# robotito.net
KiCad netlist of a schematic drawn in EAGLE
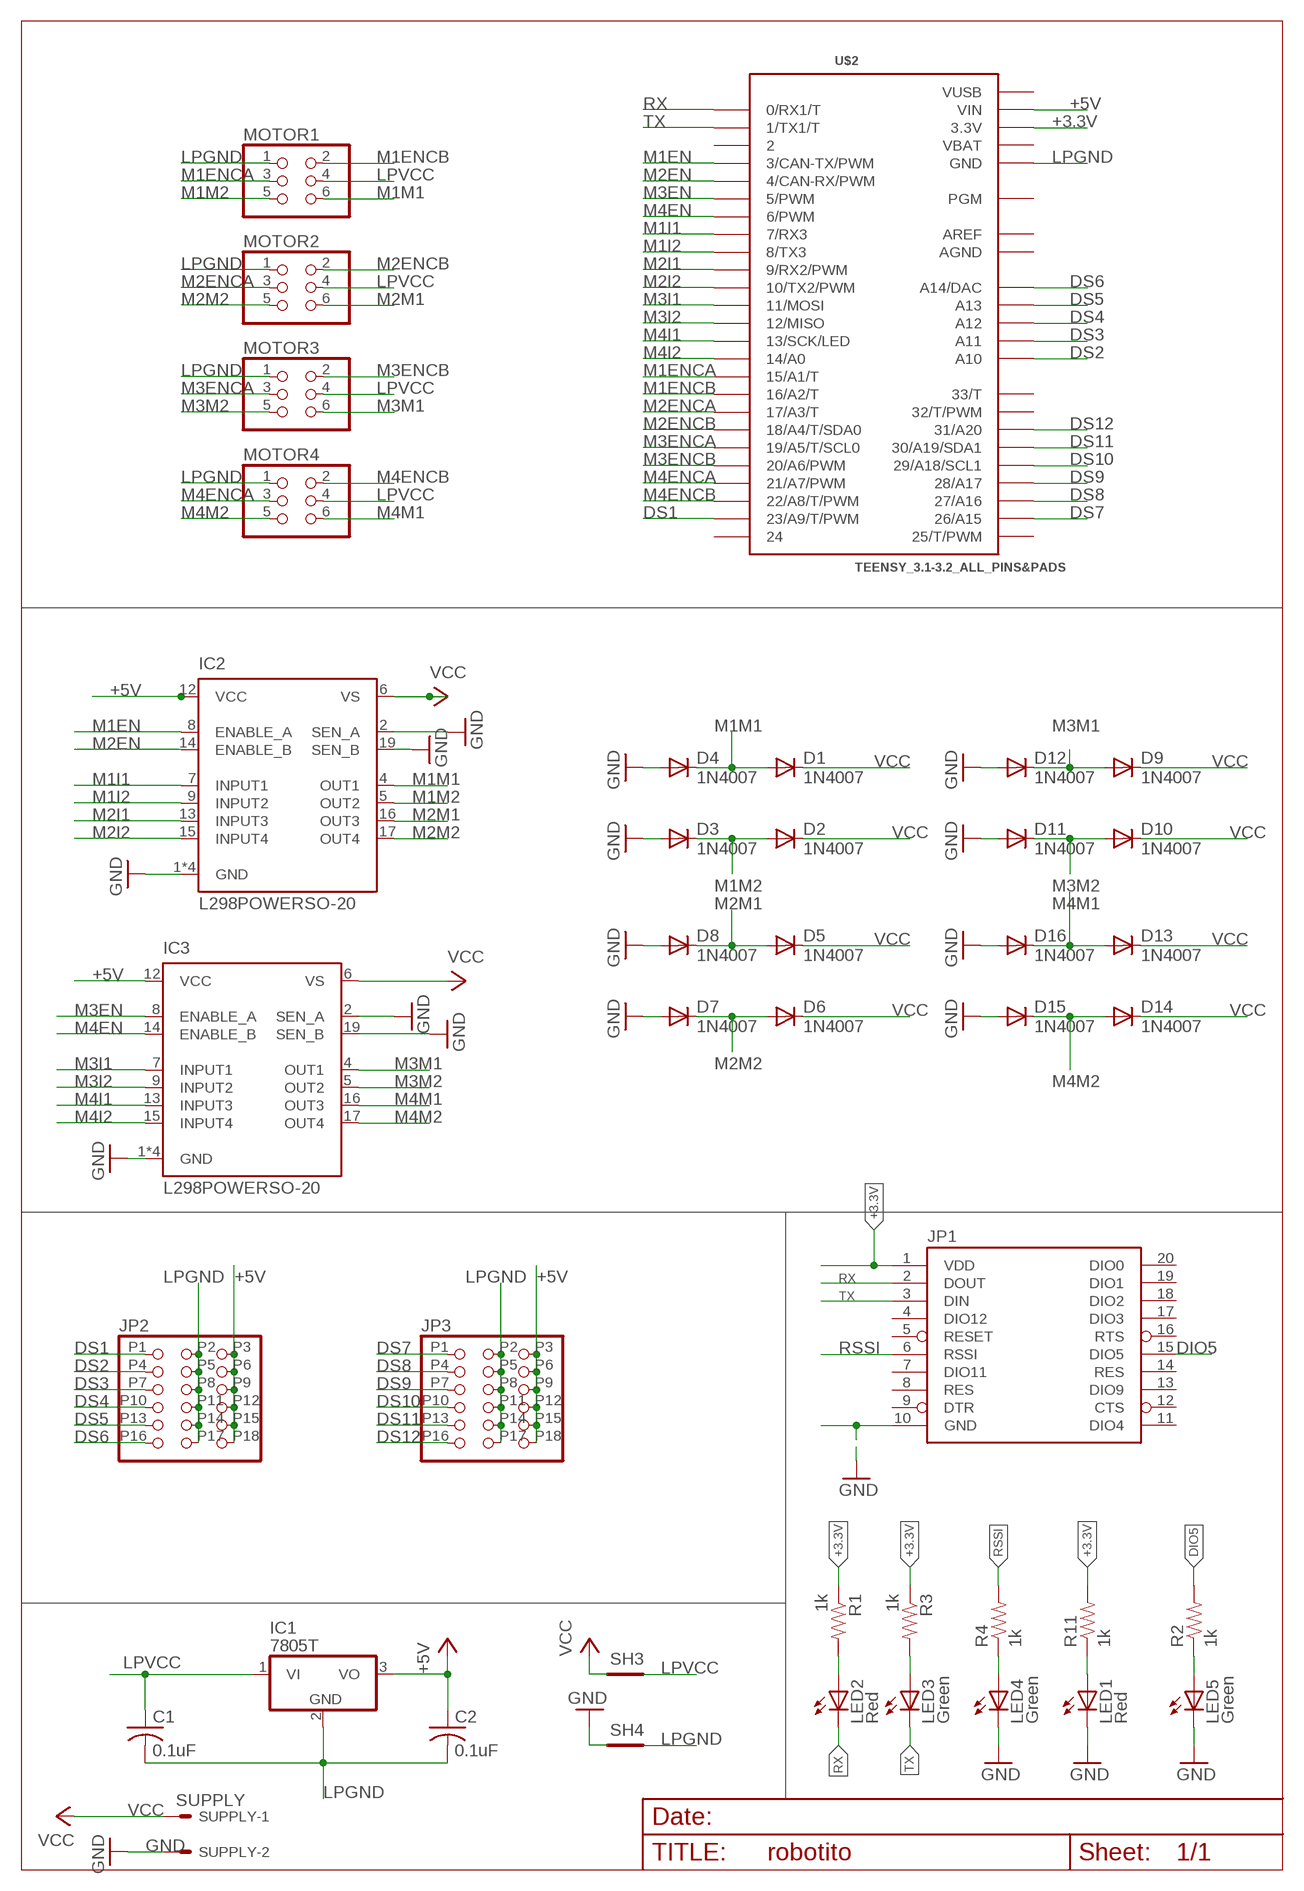
[diagram p0: schematic, sheet 1]

(export (version "E")
  (design (tool "Eeschema 10.0.6"))
  (components
    (comp (ref "C1")
      (value "0.1uF")
      (footprint "eagle-import:C0805")
      (libsource (lib "eagle-import") (part "C-USC0805"))
    )
    (comp (ref "C2")
      (value "0.1uF")
      (footprint "eagle-import:C0805")
      (libsource (lib "eagle-import") (part "C-USC0805"))
    )
    (comp (ref "D1")
      (value "1N4007")
      (footprint "eagle-import:DO41-10")
      (libsource (lib "eagle-import") (part "1N4004"))
    )
    (comp (ref "D2")
      (value "1N4007")
      (footprint "eagle-import:DO41-10")
      (libsource (lib "eagle-import") (part "1N4004"))
    )
    (comp (ref "D3")
      (value "1N4007")
      (footprint "eagle-import:DO41-10")
      (libsource (lib "eagle-import") (part "1N4004"))
    )
    (comp (ref "D4")
      (value "1N4007")
      (footprint "eagle-import:DO41-10")
      (libsource (lib "eagle-import") (part "1N4004"))
    )
    (comp (ref "D5")
      (value "1N4007")
      (footprint "eagle-import:DO41-10")
      (libsource (lib "eagle-import") (part "1N4004"))
    )
    (comp (ref "D6")
      (value "1N4007")
      (footprint "eagle-import:DO41-10")
      (libsource (lib "eagle-import") (part "1N4004"))
    )
    (comp (ref "D7")
      (value "1N4007")
      (footprint "eagle-import:DO41-10")
      (libsource (lib "eagle-import") (part "1N4004"))
    )
    (comp (ref "D8")
      (value "1N4007")
      (footprint "eagle-import:DO41-10")
      (libsource (lib "eagle-import") (part "1N4004"))
    )
    (comp (ref "D9")
      (value "1N4007")
      (footprint "eagle-import:DO41-10")
      (libsource (lib "eagle-import") (part "1N4004"))
    )
    (comp (ref "D10")
      (value "1N4007")
      (footprint "eagle-import:DO41-10")
      (libsource (lib "eagle-import") (part "1N4004"))
    )
    (comp (ref "D11")
      (value "1N4007")
      (footprint "eagle-import:DO41-10")
      (libsource (lib "eagle-import") (part "1N4004"))
    )
    (comp (ref "D12")
      (value "1N4007")
      (footprint "eagle-import:DO41-10")
      (libsource (lib "eagle-import") (part "1N4004"))
    )
    (comp (ref "D13")
      (value "1N4007")
      (footprint "eagle-import:DO41-10")
      (libsource (lib "eagle-import") (part "1N4004"))
    )
    (comp (ref "D14")
      (value "1N4007")
      (footprint "eagle-import:DO41-10")
      (libsource (lib "eagle-import") (part "1N4004"))
    )
    (comp (ref "D15")
      (value "1N4007")
      (footprint "eagle-import:DO41-10")
      (libsource (lib "eagle-import") (part "1N4004"))
    )
    (comp (ref "D16")
      (value "1N4007")
      (footprint "eagle-import:DO41-10")
      (libsource (lib "eagle-import") (part "1N4004"))
    )
    (comp (ref "IC1")
      (value "7805T")
      (footprint "eagle-import:TO220H")
      (libsource (lib "eagle-import") (part "78T05"))
    )
    (comp (ref "IC2")
      (value "L298POWERSO-20")
      (footprint "eagle-import:POWERSO-20")
      (libsource (lib "eagle-import") (part "L298POWERSO-20"))
    )
    (comp (ref "IC3")
      (value "L298POWERSO-20")
      (footprint "eagle-import:POWERSO-20")
      (libsource (lib "eagle-import") (part "L298POWERSO-20"))
    )
    (comp (ref "JP1")
      (value "XBEE-1B1")
      (footprint "eagle-import:XBEE-1")
      (libsource (lib "eagle-import") (part "XBEE-1B1"))
    )
    (comp (ref "JP2")
      (value "PINHD-2X6")
      (footprint "eagle-import:2X06")
      (libsource (lib "eagle-import") (part "PINHD-2X6"))
    )
    (comp (ref "JP3")
      (value "PINHD-2X6")
      (footprint "eagle-import:2X06")
      (libsource (lib "eagle-import") (part "PINHD-2X6"))
    )
    (comp (ref "LED1")
      (value "Red")
      (footprint "eagle-import:LED-0603")
      (libsource (lib "eagle-import") (part "LED-RED0603"))
    )
    (comp (ref "LED2")
      (value "Red")
      (footprint "eagle-import:LED-0603")
      (libsource (lib "eagle-import") (part "LED-RED0603"))
    )
    (comp (ref "LED3")
      (value "Green")
      (footprint "eagle-import:LED-0603")
      (libsource (lib "eagle-import") (part "LED-GREEN0603"))
    )
    (comp (ref "LED4")
      (value "Green")
      (footprint "eagle-import:LED-0603")
      (libsource (lib "eagle-import") (part "LED-GREEN0603"))
    )
    (comp (ref "LED5")
      (value "Green")
      (footprint "eagle-import:LED-0603")
      (libsource (lib "eagle-import") (part "LED-GREEN0603"))
    )
    (comp (ref "MOTOR1")
      (value "PINHD-2X3")
      (footprint "eagle-import:2X03")
      (libsource (lib "eagle-import") (part "PINHD-2X3"))
    )
    (comp (ref "MOTOR2")
      (value "PINHD-2X3")
      (footprint "eagle-import:2X03")
      (libsource (lib "eagle-import") (part "PINHD-2X3"))
    )
    (comp (ref "MOTOR3")
      (value "PINHD-2X3")
      (footprint "eagle-import:2X03")
      (libsource (lib "eagle-import") (part "PINHD-2X3"))
    )
    (comp (ref "MOTOR4")
      (value "PINHD-2X3")
      (footprint "eagle-import:2X03")
      (libsource (lib "eagle-import") (part "PINHD-2X3"))
    )
    (comp (ref "R1")
      (value "1k")
      (footprint "eagle-import:0603-RES")
      (libsource (lib "eagle-import") (part "1KOHM1/10W1%(0603)"))
    )
    (comp (ref "R2")
      (value "1k")
      (footprint "eagle-import:0603-RES")
      (libsource (lib "eagle-import") (part "1KOHM1/10W1%(0603)"))
    )
    (comp (ref "R3")
      (value "1k")
      (footprint "eagle-import:0603-RES")
      (libsource (lib "eagle-import") (part "1KOHM1/10W1%(0603)"))
    )
    (comp (ref "R4")
      (value "1k")
      (footprint "eagle-import:0603-RES")
      (libsource (lib "eagle-import") (part "1KOHM1/10W1%(0603)"))
    )
    (comp (ref "R11")
      (value "1k")
      (footprint "eagle-import:0603-RES")
      (libsource (lib "eagle-import") (part "1KOHM1/10W1%(0603)"))
    )
    (comp (ref "SH3")
      (value "SHORT-HT5")
      (footprint "eagle-import:SHORT_TOP-50")
      (libsource (lib "eagle-import") (part "SHORT-HT5"))
    )
    (comp (ref "SH4")
      (value "SHORT-HT5")
      (footprint "eagle-import:SHORT_TOP-50")
      (libsource (lib "eagle-import") (part "SHORT-HT5"))
    )
    (comp (ref "SUPPLY")
      (value "SUPPLY")
      (footprint "eagle-import:6410-02")
      (libsource (lib "eagle-import") (part "22-?-0227-2021"))
    )
    (comp (ref "U$2")
      (value "TEENSY_3.1-3.2_ALL_PINS&PADS")
      (footprint "eagle-import:TEENSY_3.0-3.2_ALL_PINS_&_PADS")
      (libsource (lib "eagle-import") (part "TEENSY_3.1-3.2_ALL_PINS&PADS"))
    )
  )
  (nets
    (net (code "1") (name "+3.3V") (class "Default")
      (node (ref "JP1") (pin "1") (pinfunction "VDD_1") (pintype "power_in"))
      (node (ref "R1") (pin "1") (pinfunction "1_1") (pintype "passive"))
      (node (ref "R11") (pin "2") (pinfunction "2_2") (pintype "passive"))
      (node (ref "R3") (pin "1") (pinfunction "1_1") (pintype "passive"))
      (node (ref "U$2") (pin "3.3V") (pinfunction "3.3V_3.3V") (pintype "power_in"))
      (node (ref "U$2") (pin "3.3V1") (pinfunction "3.3V_3.3V1") (pintype "power_in"))
      (node (ref "U$2") (pin "3.3V2") (pinfunction "3.3V_3.3V2") (pintype "power_in"))
    )
    (net (code "2") (name "+5V") (class "Default")
      (node (ref "C2") (pin "1") (pinfunction "1_1") (pintype "passive"))
      (node (ref "IC1") (pin "3") (pinfunction "VO_3") (pintype "passive"))
      (node (ref "IC2") (pin "12") (pinfunction "VCC_12") (pintype "power_in"))
      (node (ref "IC3") (pin "12") (pinfunction "VCC_12") (pintype "power_in"))
      (node (ref "JP2") (pin "P12") (pinfunction "P12_P12") (pintype "passive"))
      (node (ref "JP2") (pin "P15") (pinfunction "P15_P15") (pintype "passive"))
      (node (ref "JP2") (pin "P18") (pinfunction "P18_P18") (pintype "passive"))
      (node (ref "JP2") (pin "P3") (pinfunction "P3_P3") (pintype "passive"))
      (node (ref "JP2") (pin "P6") (pinfunction "P6_P6") (pintype "passive"))
      (node (ref "JP2") (pin "P9") (pinfunction "P9_P9") (pintype "passive"))
      (node (ref "JP3") (pin "P12") (pinfunction "P12_P12") (pintype "passive"))
      (node (ref "JP3") (pin "P15") (pinfunction "P15_P15") (pintype "passive"))
      (node (ref "JP3") (pin "P18") (pinfunction "P18_P18") (pintype "passive"))
      (node (ref "JP3") (pin "P3") (pinfunction "P3_P3") (pintype "passive"))
      (node (ref "JP3") (pin "P6") (pinfunction "P6_P6") (pintype "passive"))
      (node (ref "JP3") (pin "P9") (pinfunction "P9_P9") (pintype "passive"))
      (node (ref "U$2") (pin "VIN") (pinfunction "VIN_VIN") (pintype "power_in"))
    )
    (net (code "3") (name "/AGND") (class "Default")
      (node (ref "U$2") (pin "AGND") (pinfunction "AGND_AGND") (pintype "power_in"))
    )
    (net (code "4") (name "/AREF") (class "Default")
      (node (ref "U$2") (pin "AREF") (pinfunction "AREF_AREF") (pintype "power_in"))
    )
    (net (code "5") (name "/DS1") (class "Default")
      (node (ref "JP2") (pin "P1") (pinfunction "P1_P1") (pintype "passive"))
      (node (ref "U$2") (pin "23/A9") (pinfunction "23/A9/T/PWM_23/A9") (pintype "bidirectional"))
    )
    (net (code "6") (name "/DS2") (class "Default")
      (node (ref "JP2") (pin "P4") (pinfunction "P4_P4") (pintype "passive"))
      (node (ref "U$2") (pin "A10") (pinfunction "A10_A10") (pintype "bidirectional"))
    )
    (net (code "7") (name "/DS3") (class "Default")
      (node (ref "JP2") (pin "P7") (pinfunction "P7_P7") (pintype "passive"))
      (node (ref "U$2") (pin "A11") (pinfunction "A11_A11") (pintype "bidirectional"))
    )
    (net (code "8") (name "/DS4") (class "Default")
      (node (ref "JP2") (pin "P10") (pinfunction "P10_P10") (pintype "passive"))
      (node (ref "U$2") (pin "A12") (pinfunction "A12_A12") (pintype "bidirectional"))
    )
    (net (code "9") (name "/DS5") (class "Default")
      (node (ref "JP2") (pin "P13") (pinfunction "P13_P13") (pintype "passive"))
      (node (ref "U$2") (pin "A13") (pinfunction "A13_A13") (pintype "bidirectional"))
    )
    (net (code "10") (name "/DS6") (class "Default")
      (node (ref "JP2") (pin "P16") (pinfunction "P16_P16") (pintype "passive"))
      (node (ref "U$2") (pin "RESET/DAC") (pinfunction "A14/DAC_RESET/DAC") (pintype "bidirectional"))
    )
    (net (code "11") (name "/DS7") (class "Default")
      (node (ref "JP3") (pin "P1") (pinfunction "P1_P1") (pintype "passive"))
      (node (ref "U$2") (pin "26") (pinfunction "26/A15_26") (pintype "bidirectional"))
    )
    (net (code "12") (name "/DS8") (class "Default")
      (node (ref "JP3") (pin "P4") (pinfunction "P4_P4") (pintype "passive"))
      (node (ref "U$2") (pin "27") (pinfunction "27/A16_27") (pintype "bidirectional"))
    )
    (net (code "13") (name "/DS9") (class "Default")
      (node (ref "JP3") (pin "P7") (pinfunction "P7_P7") (pintype "passive"))
      (node (ref "U$2") (pin "28") (pinfunction "28/A17_28") (pintype "bidirectional"))
    )
    (net (code "14") (name "/DS10") (class "Default")
      (node (ref "JP3") (pin "P10") (pinfunction "P10_P10") (pintype "passive"))
      (node (ref "U$2") (pin "29") (pinfunction "29/A18/SCL1_29") (pintype "bidirectional"))
    )
    (net (code "15") (name "/DS11") (class "Default")
      (node (ref "JP3") (pin "P13") (pinfunction "P13_P13") (pintype "passive"))
      (node (ref "U$2") (pin "30") (pinfunction "30/A19/SDA1_30") (pintype "bidirectional"))
    )
    (net (code "16") (name "/DS12") (class "Default")
      (node (ref "JP3") (pin "P16") (pinfunction "P16_P16") (pintype "passive"))
      (node (ref "U$2") (pin "31") (pinfunction "31/A20_31") (pintype "bidirectional"))
    )
    (net (code "17") (name "/LPGND") (class "Default")
      (node (ref "C1") (pin "2") (pinfunction "2_2") (pintype "passive"))
      (node (ref "C2") (pin "2") (pinfunction "2_2") (pintype "passive"))
      (node (ref "IC1") (pin "2") (pinfunction "GND_2") (pintype "passive"))
      (node (ref "JP2") (pin "P11") (pinfunction "P11_P11") (pintype "passive"))
      (node (ref "JP2") (pin "P14") (pinfunction "P14_P14") (pintype "passive"))
      (node (ref "JP2") (pin "P17") (pinfunction "P17_P17") (pintype "passive"))
      (node (ref "JP2") (pin "P2") (pinfunction "P2_P2") (pintype "passive"))
      (node (ref "JP2") (pin "P5") (pinfunction "P5_P5") (pintype "passive"))
      (node (ref "JP2") (pin "P8") (pinfunction "P8_P8") (pintype "passive"))
      (node (ref "JP3") (pin "P11") (pinfunction "P11_P11") (pintype "passive"))
      (node (ref "JP3") (pin "P14") (pinfunction "P14_P14") (pintype "passive"))
      (node (ref "JP3") (pin "P17") (pinfunction "P17_P17") (pintype "passive"))
      (node (ref "JP3") (pin "P2") (pinfunction "P2_P2") (pintype "passive"))
      (node (ref "JP3") (pin "P5") (pinfunction "P5_P5") (pintype "passive"))
      (node (ref "JP3") (pin "P8") (pinfunction "P8_P8") (pintype "passive"))
      (node (ref "MOTOR1") (pin "1") (pinfunction "1_1") (pintype "passive"))
      (node (ref "MOTOR2") (pin "1") (pinfunction "1_1") (pintype "passive"))
      (node (ref "MOTOR3") (pin "1") (pinfunction "1_1") (pintype "passive"))
      (node (ref "MOTOR4") (pin "1") (pinfunction "1_1") (pintype "passive"))
      (node (ref "SH4") (pin "2") (pinfunction "P$2_2") (pintype "bidirectional"))
      (node (ref "U$2") (pin "GND") (pinfunction "GND_GND") (pintype "power_in"))
      (node (ref "U$2") (pin "GND1") (pinfunction "GND_GND1") (pintype "power_in"))
      (node (ref "U$2") (pin "GND2") (pinfunction "GND_GND2") (pintype "power_in"))
    )
    (net (code "18") (name "/LPVCC") (class "Default")
      (node (ref "C1") (pin "1") (pinfunction "1_1") (pintype "passive"))
      (node (ref "IC1") (pin "1") (pinfunction "VI_1") (pintype "input"))
      (node (ref "MOTOR1") (pin "4") (pinfunction "4_4") (pintype "passive"))
      (node (ref "MOTOR2") (pin "4") (pinfunction "4_4") (pintype "passive"))
      (node (ref "MOTOR3") (pin "4") (pinfunction "4_4") (pintype "passive"))
      (node (ref "MOTOR4") (pin "4") (pinfunction "4_4") (pintype "passive"))
      (node (ref "SH3") (pin "2") (pinfunction "P$2_2") (pintype "bidirectional"))
    )
    (net (code "19") (name "/M1EN") (class "Default")
      (node (ref "IC2") (pin "8") (pinfunction "ENABLE_A_8") (pintype "input"))
      (node (ref "U$2") (pin "3") (pinfunction "3/CAN-TX/PWM_3") (pintype "bidirectional"))
    )
    (net (code "20") (name "/M1ENCA") (class "Default")
      (node (ref "MOTOR1") (pin "3") (pinfunction "3_3") (pintype "passive"))
      (node (ref "U$2") (pin "15/A1") (pinfunction "15/A1/T_15/A1") (pintype "bidirectional"))
    )
    (net (code "21") (name "/M1ENCB") (class "Default")
      (node (ref "MOTOR1") (pin "2") (pinfunction "2_2") (pintype "passive"))
      (node (ref "U$2") (pin "16/A2") (pinfunction "16/A2/T_16/A2") (pintype "bidirectional"))
    )
    (net (code "22") (name "/M1I1") (class "Default")
      (node (ref "IC2") (pin "7") (pinfunction "INPUT1_7") (pintype "input"))
      (node (ref "U$2") (pin "7") (pinfunction "7/RX3_7") (pintype "bidirectional"))
    )
    (net (code "23") (name "/M1I2") (class "Default")
      (node (ref "IC2") (pin "9") (pinfunction "INPUT2_9") (pintype "input"))
      (node (ref "U$2") (pin "8") (pinfunction "8/TX3_8") (pintype "bidirectional"))
    )
    (net (code "24") (name "/M1M1") (class "Default")
      (node (ref "D1") (pin "A") (pinfunction "A_A") (pintype "passive"))
      (node (ref "D4") (pin "C") (pinfunction "C_C") (pintype "passive"))
      (node (ref "IC2") (pin "4") (pinfunction "OUT1_4") (pintype "output"))
      (node (ref "MOTOR1") (pin "6") (pinfunction "6_6") (pintype "passive"))
    )
    (net (code "25") (name "/M1M2") (class "Default")
      (node (ref "D2") (pin "A") (pinfunction "A_A") (pintype "passive"))
      (node (ref "D3") (pin "C") (pinfunction "C_C") (pintype "passive"))
      (node (ref "IC2") (pin "5") (pinfunction "OUT2_5") (pintype "output"))
      (node (ref "MOTOR1") (pin "5") (pinfunction "5_5") (pintype "passive"))
    )
    (net (code "26") (name "/M2EN") (class "Default")
      (node (ref "IC2") (pin "14") (pinfunction "ENABLE_B_14") (pintype "input"))
      (node (ref "U$2") (pin "4") (pinfunction "4/CAN-RX/PWM_4") (pintype "bidirectional"))
    )
    (net (code "27") (name "/M2ENCA") (class "Default")
      (node (ref "MOTOR2") (pin "3") (pinfunction "3_3") (pintype "passive"))
      (node (ref "U$2") (pin "17/A3") (pinfunction "17/A3/T_17/A3") (pintype "bidirectional"))
    )
    (net (code "28") (name "/M2ENCB") (class "Default")
      (node (ref "MOTOR2") (pin "2") (pinfunction "2_2") (pintype "passive"))
      (node (ref "U$2") (pin "18/A4") (pinfunction "18/A4/T/SDA0_18/A4") (pintype "bidirectional"))
    )
    (net (code "29") (name "/M2I1") (class "Default")
      (node (ref "IC2") (pin "13") (pinfunction "INPUT3_13") (pintype "input"))
      (node (ref "U$2") (pin "9") (pinfunction "9/RX2/PWM_9") (pintype "bidirectional"))
    )
    (net (code "30") (name "/M2I2") (class "Default")
      (node (ref "IC2") (pin "15") (pinfunction "INPUT4_15") (pintype "input"))
      (node (ref "U$2") (pin "10") (pinfunction "10/TX2/PWM_10") (pintype "bidirectional"))
    )
    (net (code "31") (name "/M2M1") (class "Default")
      (node (ref "D5") (pin "A") (pinfunction "A_A") (pintype "passive"))
      (node (ref "D8") (pin "C") (pinfunction "C_C") (pintype "passive"))
      (node (ref "IC2") (pin "16") (pinfunction "OUT3_16") (pintype "output"))
      (node (ref "MOTOR2") (pin "6") (pinfunction "6_6") (pintype "passive"))
    )
    (net (code "32") (name "/M2M2") (class "Default")
      (node (ref "D6") (pin "A") (pinfunction "A_A") (pintype "passive"))
      (node (ref "D7") (pin "C") (pinfunction "C_C") (pintype "passive"))
      (node (ref "IC2") (pin "17") (pinfunction "OUT4_17") (pintype "output"))
      (node (ref "MOTOR2") (pin "5") (pinfunction "5_5") (pintype "passive"))
    )
    (net (code "33") (name "/M3EN") (class "Default")
      (node (ref "IC3") (pin "8") (pinfunction "ENABLE_A_8") (pintype "input"))
      (node (ref "U$2") (pin "5") (pinfunction "5/PWM_5") (pintype "bidirectional"))
    )
    (net (code "34") (name "/M3ENCA") (class "Default")
      (node (ref "MOTOR3") (pin "3") (pinfunction "3_3") (pintype "passive"))
      (node (ref "U$2") (pin "19/A5") (pinfunction "19/A5/T/SCL0_19/A5") (pintype "bidirectional"))
    )
    (net (code "35") (name "/M3ENCB") (class "Default")
      (node (ref "MOTOR3") (pin "2") (pinfunction "2_2") (pintype "passive"))
      (node (ref "U$2") (pin "20/A6") (pinfunction "20/A6/PWM_20/A6") (pintype "bidirectional"))
    )
    (net (code "36") (name "/M3I1") (class "Default")
      (node (ref "IC3") (pin "7") (pinfunction "INPUT1_7") (pintype "input"))
      (node (ref "U$2") (pin "11") (pinfunction "11/MOSI_11") (pintype "bidirectional"))
    )
    (net (code "37") (name "/M3I2") (class "Default")
      (node (ref "IC3") (pin "9") (pinfunction "INPUT2_9") (pintype "input"))
      (node (ref "U$2") (pin "12") (pinfunction "12/MISO_12") (pintype "bidirectional"))
    )
    (net (code "38") (name "/M3M1") (class "Default")
      (node (ref "D12") (pin "C") (pinfunction "C_C") (pintype "passive"))
      (node (ref "D9") (pin "A") (pinfunction "A_A") (pintype "passive"))
      (node (ref "IC3") (pin "4") (pinfunction "OUT1_4") (pintype "output"))
      (node (ref "MOTOR3") (pin "6") (pinfunction "6_6") (pintype "passive"))
    )
    (net (code "39") (name "/M3M2") (class "Default")
      (node (ref "D10") (pin "A") (pinfunction "A_A") (pintype "passive"))
      (node (ref "D11") (pin "C") (pinfunction "C_C") (pintype "passive"))
      (node (ref "IC3") (pin "5") (pinfunction "OUT2_5") (pintype "output"))
      (node (ref "MOTOR3") (pin "5") (pinfunction "5_5") (pintype "passive"))
    )
    (net (code "40") (name "/M4EN") (class "Default")
      (node (ref "IC3") (pin "14") (pinfunction "ENABLE_B_14") (pintype "input"))
      (node (ref "U$2") (pin "6") (pinfunction "6/PWM_6") (pintype "bidirectional"))
    )
    (net (code "41") (name "/M4ENCA") (class "Default")
      (node (ref "MOTOR4") (pin "3") (pinfunction "3_3") (pintype "passive"))
      (node (ref "U$2") (pin "21/A7") (pinfunction "21/A7/PWM_21/A7") (pintype "bidirectional"))
    )
    (net (code "42") (name "/M4ENCB") (class "Default")
      (node (ref "MOTOR4") (pin "2") (pinfunction "2_2") (pintype "passive"))
      (node (ref "U$2") (pin "22/A8") (pinfunction "22/A8/T/PWM_22/A8") (pintype "bidirectional"))
    )
    (net (code "43") (name "/M4I1") (class "Default")
      (node (ref "IC3") (pin "13") (pinfunction "INPUT3_13") (pintype "input"))
      (node (ref "U$2") (pin "13") (pinfunction "13/SCK/LED_13") (pintype "bidirectional"))
    )
    (net (code "44") (name "/M4I2") (class "Default")
      (node (ref "IC3") (pin "15") (pinfunction "INPUT4_15") (pintype "input"))
      (node (ref "U$2") (pin "14/A0") (pinfunction "14/A0_14/A0") (pintype "bidirectional"))
    )
    (net (code "45") (name "/M4M1") (class "Default")
      (node (ref "D13") (pin "A") (pinfunction "A_A") (pintype "passive"))
      (node (ref "D16") (pin "C") (pinfunction "C_C") (pintype "passive"))
      (node (ref "IC3") (pin "16") (pinfunction "OUT3_16") (pintype "output"))
      (node (ref "MOTOR4") (pin "6") (pinfunction "6_6") (pintype "passive"))
    )
    (net (code "46") (name "/M4M2") (class "Default")
      (node (ref "D14") (pin "A") (pinfunction "A_A") (pintype "passive"))
      (node (ref "D15") (pin "C") (pinfunction "C_C") (pintype "passive"))
      (node (ref "IC3") (pin "17") (pinfunction "OUT4_17") (pintype "output"))
      (node (ref "MOTOR4") (pin "5") (pinfunction "5_5") (pintype "passive"))
    )
    (net (code "47") (name "/VBAT") (class "Default")
      (node (ref "U$2") (pin "VBAT") (pinfunction "VBAT_VBAT") (pintype "power_in"))
    )
    (net (code "48") (name "/VUSB") (class "Default")
      (node (ref "U$2") (pin "VUSB") (pinfunction "VUSB_VUSB") (pintype "power_in"))
    )
    (net (code "49") (name "DIO5") (class "Default")
      (node (ref "JP1") (pin "15") (pinfunction "DIO5_15") (pintype "bidirectional"))
      (node (ref "R2") (pin "2") (pinfunction "2_2") (pintype "passive"))
    )
    (net (code "50") (name "GND") (class "Default")
      (node (ref "D11") (pin "A") (pinfunction "A_A") (pintype "passive"))
      (node (ref "D12") (pin "A") (pinfunction "A_A") (pintype "passive"))
      (node (ref "D15") (pin "A") (pinfunction "A_A") (pintype "passive"))
      (node (ref "D16") (pin "A") (pinfunction "A_A") (pintype "passive"))
      (node (ref "D3") (pin "A") (pinfunction "A_A") (pintype "passive"))
      (node (ref "D4") (pin "A") (pinfunction "A_A") (pintype "passive"))
      (node (ref "D7") (pin "A") (pinfunction "A_A") (pintype "passive"))
      (node (ref "D8") (pin "A") (pinfunction "A_A") (pintype "passive"))
      (node (ref "IC2") (pin "1") (pinfunction "GND_1") (pintype "power_in"))
      (node (ref "IC2") (pin "10") (pinfunction "GND_10") (pintype "power_in"))
      (node (ref "IC2") (pin "11") (pinfunction "GND_11") (pintype "power_in"))
      (node (ref "IC2") (pin "19") (pinfunction "SEN_B_19") (pintype "input"))
      (node (ref "IC2") (pin "2") (pinfunction "SEN_A_2") (pintype "input"))
      (node (ref "IC2") (pin "20") (pinfunction "GND_20") (pintype "power_in"))
      (node (ref "IC3") (pin "1") (pinfunction "GND_1") (pintype "power_in"))
      (node (ref "IC3") (pin "10") (pinfunction "GND_10") (pintype "power_in"))
      (node (ref "IC3") (pin "11") (pinfunction "GND_11") (pintype "power_in"))
      (node (ref "IC3") (pin "19") (pinfunction "SEN_B_19") (pintype "input"))
      (node (ref "IC3") (pin "2") (pinfunction "SEN_A_2") (pintype "input"))
      (node (ref "IC3") (pin "20") (pinfunction "GND_20") (pintype "power_in"))
      (node (ref "JP1") (pin "10") (pinfunction "GND_10") (pintype "power_in"))
      (node (ref "LED1") (pin "C") (pinfunction "C_C") (pintype "passive"))
      (node (ref "LED4") (pin "C") (pinfunction "C_C") (pintype "passive"))
      (node (ref "LED5") (pin "C") (pinfunction "C_C") (pintype "passive"))
      (node (ref "SH4") (pin "1") (pinfunction "P$1_1") (pintype "bidirectional"))
      (node (ref "SUPPLY") (pin "2") (pinfunction "S_2") (pintype "passive"))
    )
    (net (code "51") (name "Net-(LED1-PadA)") (class "Default")
      (node (ref "LED1") (pin "A") (pinfunction "A_A") (pintype "passive"))
      (node (ref "R11") (pin "1") (pinfunction "1_1") (pintype "passive"))
    )
    (net (code "52") (name "Net-(LED2-PadA)") (class "Default")
      (node (ref "LED2") (pin "A") (pinfunction "A_A") (pintype "passive"))
      (node (ref "R1") (pin "2") (pinfunction "2_2") (pintype "passive"))
    )
    (net (code "53") (name "Net-(LED3-PadA)") (class "Default")
      (node (ref "LED3") (pin "A") (pinfunction "A_A") (pintype "passive"))
      (node (ref "R3") (pin "2") (pinfunction "2_2") (pintype "passive"))
    )
    (net (code "54") (name "Net-(LED4-PadA)") (class "Default")
      (node (ref "LED4") (pin "A") (pinfunction "A_A") (pintype "passive"))
      (node (ref "R4") (pin "1") (pinfunction "1_1") (pintype "passive"))
    )
    (net (code "55") (name "Net-(LED5-PadA)") (class "Default")
      (node (ref "LED5") (pin "A") (pinfunction "A_A") (pintype "passive"))
      (node (ref "R2") (pin "1") (pinfunction "1_1") (pintype "passive"))
    )
    (net (code "56") (name "RSSI") (class "Default")
      (node (ref "JP1") (pin "6") (pinfunction "RSSI_6") (pintype "bidirectional"))
      (node (ref "R4") (pin "2") (pinfunction "2_2") (pintype "passive"))
    )
    (net (code "57") (name "RX") (class "Default")
      (node (ref "JP1") (pin "2") (pinfunction "DOUT_2") (pintype "output"))
      (node (ref "LED2") (pin "C") (pinfunction "C_C") (pintype "passive"))
      (node (ref "U$2") (pin "0") (pinfunction "0/RX1/T_0") (pintype "bidirectional"))
    )
    (net (code "58") (name "TX") (class "Default")
      (node (ref "JP1") (pin "3") (pinfunction "DIN_3") (pintype "input"))
      (node (ref "LED3") (pin "C") (pinfunction "C_C") (pintype "passive"))
      (node (ref "U$2") (pin "1") (pinfunction "1/TX1/T_1") (pintype "bidirectional"))
    )
    (net (code "59") (name "VCC") (class "Default")
      (node (ref "D1") (pin "C") (pinfunction "C_C") (pintype "passive"))
      (node (ref "D10") (pin "C") (pinfunction "C_C") (pintype "passive"))
      (node (ref "D13") (pin "C") (pinfunction "C_C") (pintype "passive"))
      (node (ref "D14") (pin "C") (pinfunction "C_C") (pintype "passive"))
      (node (ref "D2") (pin "C") (pinfunction "C_C") (pintype "passive"))
      (node (ref "D5") (pin "C") (pinfunction "C_C") (pintype "passive"))
      (node (ref "D6") (pin "C") (pinfunction "C_C") (pintype "passive"))
      (node (ref "D9") (pin "C") (pinfunction "C_C") (pintype "passive"))
      (node (ref "IC2") (pin "6") (pinfunction "VS_6") (pintype "power_in"))
      (node (ref "IC3") (pin "6") (pinfunction "VS_6") (pintype "power_in"))
      (node (ref "SH3") (pin "1") (pinfunction "P$1_1") (pintype "bidirectional"))
      (node (ref "SUPPLY") (pin "1") (pinfunction "S_1") (pintype "passive"))
    )
    (net (code "60") (name "unconnected-(JP1-CTS-Pad12)") (class "Default")
      (node (ref "JP1") (pin "12") (pinfunction "CTS_12") (pintype "output"))
    )
    (net (code "61") (name "unconnected-(JP1-DIO0-Pad20)") (class "Default")
      (node (ref "JP1") (pin "20") (pinfunction "DIO0_20") (pintype "bidirectional"))
    )
    (net (code "62") (name "unconnected-(JP1-DIO1-Pad19)") (class "Default")
      (node (ref "JP1") (pin "19") (pinfunction "DIO1_19") (pintype "bidirectional"))
    )
    (net (code "63") (name "unconnected-(JP1-DIO2-Pad18)") (class "Default")
      (node (ref "JP1") (pin "18") (pinfunction "DIO2_18") (pintype "bidirectional"))
    )
    (net (code "64") (name "unconnected-(JP1-DIO3-Pad17)") (class "Default")
      (node (ref "JP1") (pin "17") (pinfunction "DIO3_17") (pintype "bidirectional"))
    )
    (net (code "65") (name "unconnected-(JP1-DIO4-Pad11)") (class "Default")
      (node (ref "JP1") (pin "11") (pinfunction "DIO4_11") (pintype "bidirectional"))
    )
    (net (code "66") (name "unconnected-(JP1-DIO9-Pad13)") (class "Default")
      (node (ref "JP1") (pin "13") (pinfunction "DIO9_13") (pintype "bidirectional"))
    )
    (net (code "67") (name "unconnected-(JP1-DIO11-Pad7)") (class "Default")
      (node (ref "JP1") (pin "7") (pinfunction "DIO11_7") (pintype "bidirectional"))
    )
    (net (code "68") (name "unconnected-(JP1-DIO12-Pad4)") (class "Default")
      (node (ref "JP1") (pin "4") (pinfunction "DIO12_4") (pintype "bidirectional"))
    )
    (net (code "69") (name "unconnected-(JP1-DTR-Pad9)") (class "Default")
      (node (ref "JP1") (pin "9") (pinfunction "DTR_9") (pintype "bidirectional"))
    )
    (net (code "70") (name "unconnected-(JP1-RES-Pad8)") (class "Default")
      (node (ref "JP1") (pin "8") (pinfunction "RES_8") (pintype "bidirectional"))
    )
    (net (code "71") (name "unconnected-(JP1-RES-Pad14)") (class "Default")
      (node (ref "JP1") (pin "14") (pinfunction "RES_14") (pintype "bidirectional"))
    )
    (net (code "72") (name "unconnected-(JP1-RESET-Pad5)") (class "Default")
      (node (ref "JP1") (pin "5") (pinfunction "RESET_5") (pintype "input"))
    )
    (net (code "73") (name "unconnected-(JP1-RTS-Pad16)") (class "Default")
      (node (ref "JP1") (pin "16") (pinfunction "RTS_16") (pintype "input"))
    )
    (net (code "74") (name "unconnected-(U$2-25{slash}T{slash}PWM-Pad25)") (class "Default")
      (node (ref "U$2") (pin "25") (pinfunction "25/T/PWM_25") (pintype "bidirectional"))
    )
    (net (code "75") (name "unconnected-(U$2-32{slash}T{slash}PWM-Pad32)") (class "Default")
      (node (ref "U$2") (pin "32") (pinfunction "32/T/PWM_32") (pintype "bidirectional"))
    )
    (net (code "76") (name "unconnected-(U$2-33{slash}T-Pad33)") (class "Default")
      (node (ref "U$2") (pin "33") (pinfunction "33/T_33") (pintype "bidirectional"))
    )
    (net (code "77") (name "unconnected-(U$2-Pad2)") (class "Default")
      (node (ref "U$2") (pin "2") (pinfunction "2_2") (pintype "bidirectional"))
    )
    (net (code "78") (name "unconnected-(U$2-Pad24)") (class "Default")
      (node (ref "U$2") (pin "24") (pinfunction "24_24") (pintype "bidirectional"))
    )
    (net (code "79") (name "unconnected-(U$2-PadPGM)") (class "Default")
      (node (ref "U$2") (pin "PGM") (pinfunction "PGM_PGM") (pintype "bidirectional"))
    )
  )
)
